# design.net
KiCad netlist of a schematic drawn in Altium Designer
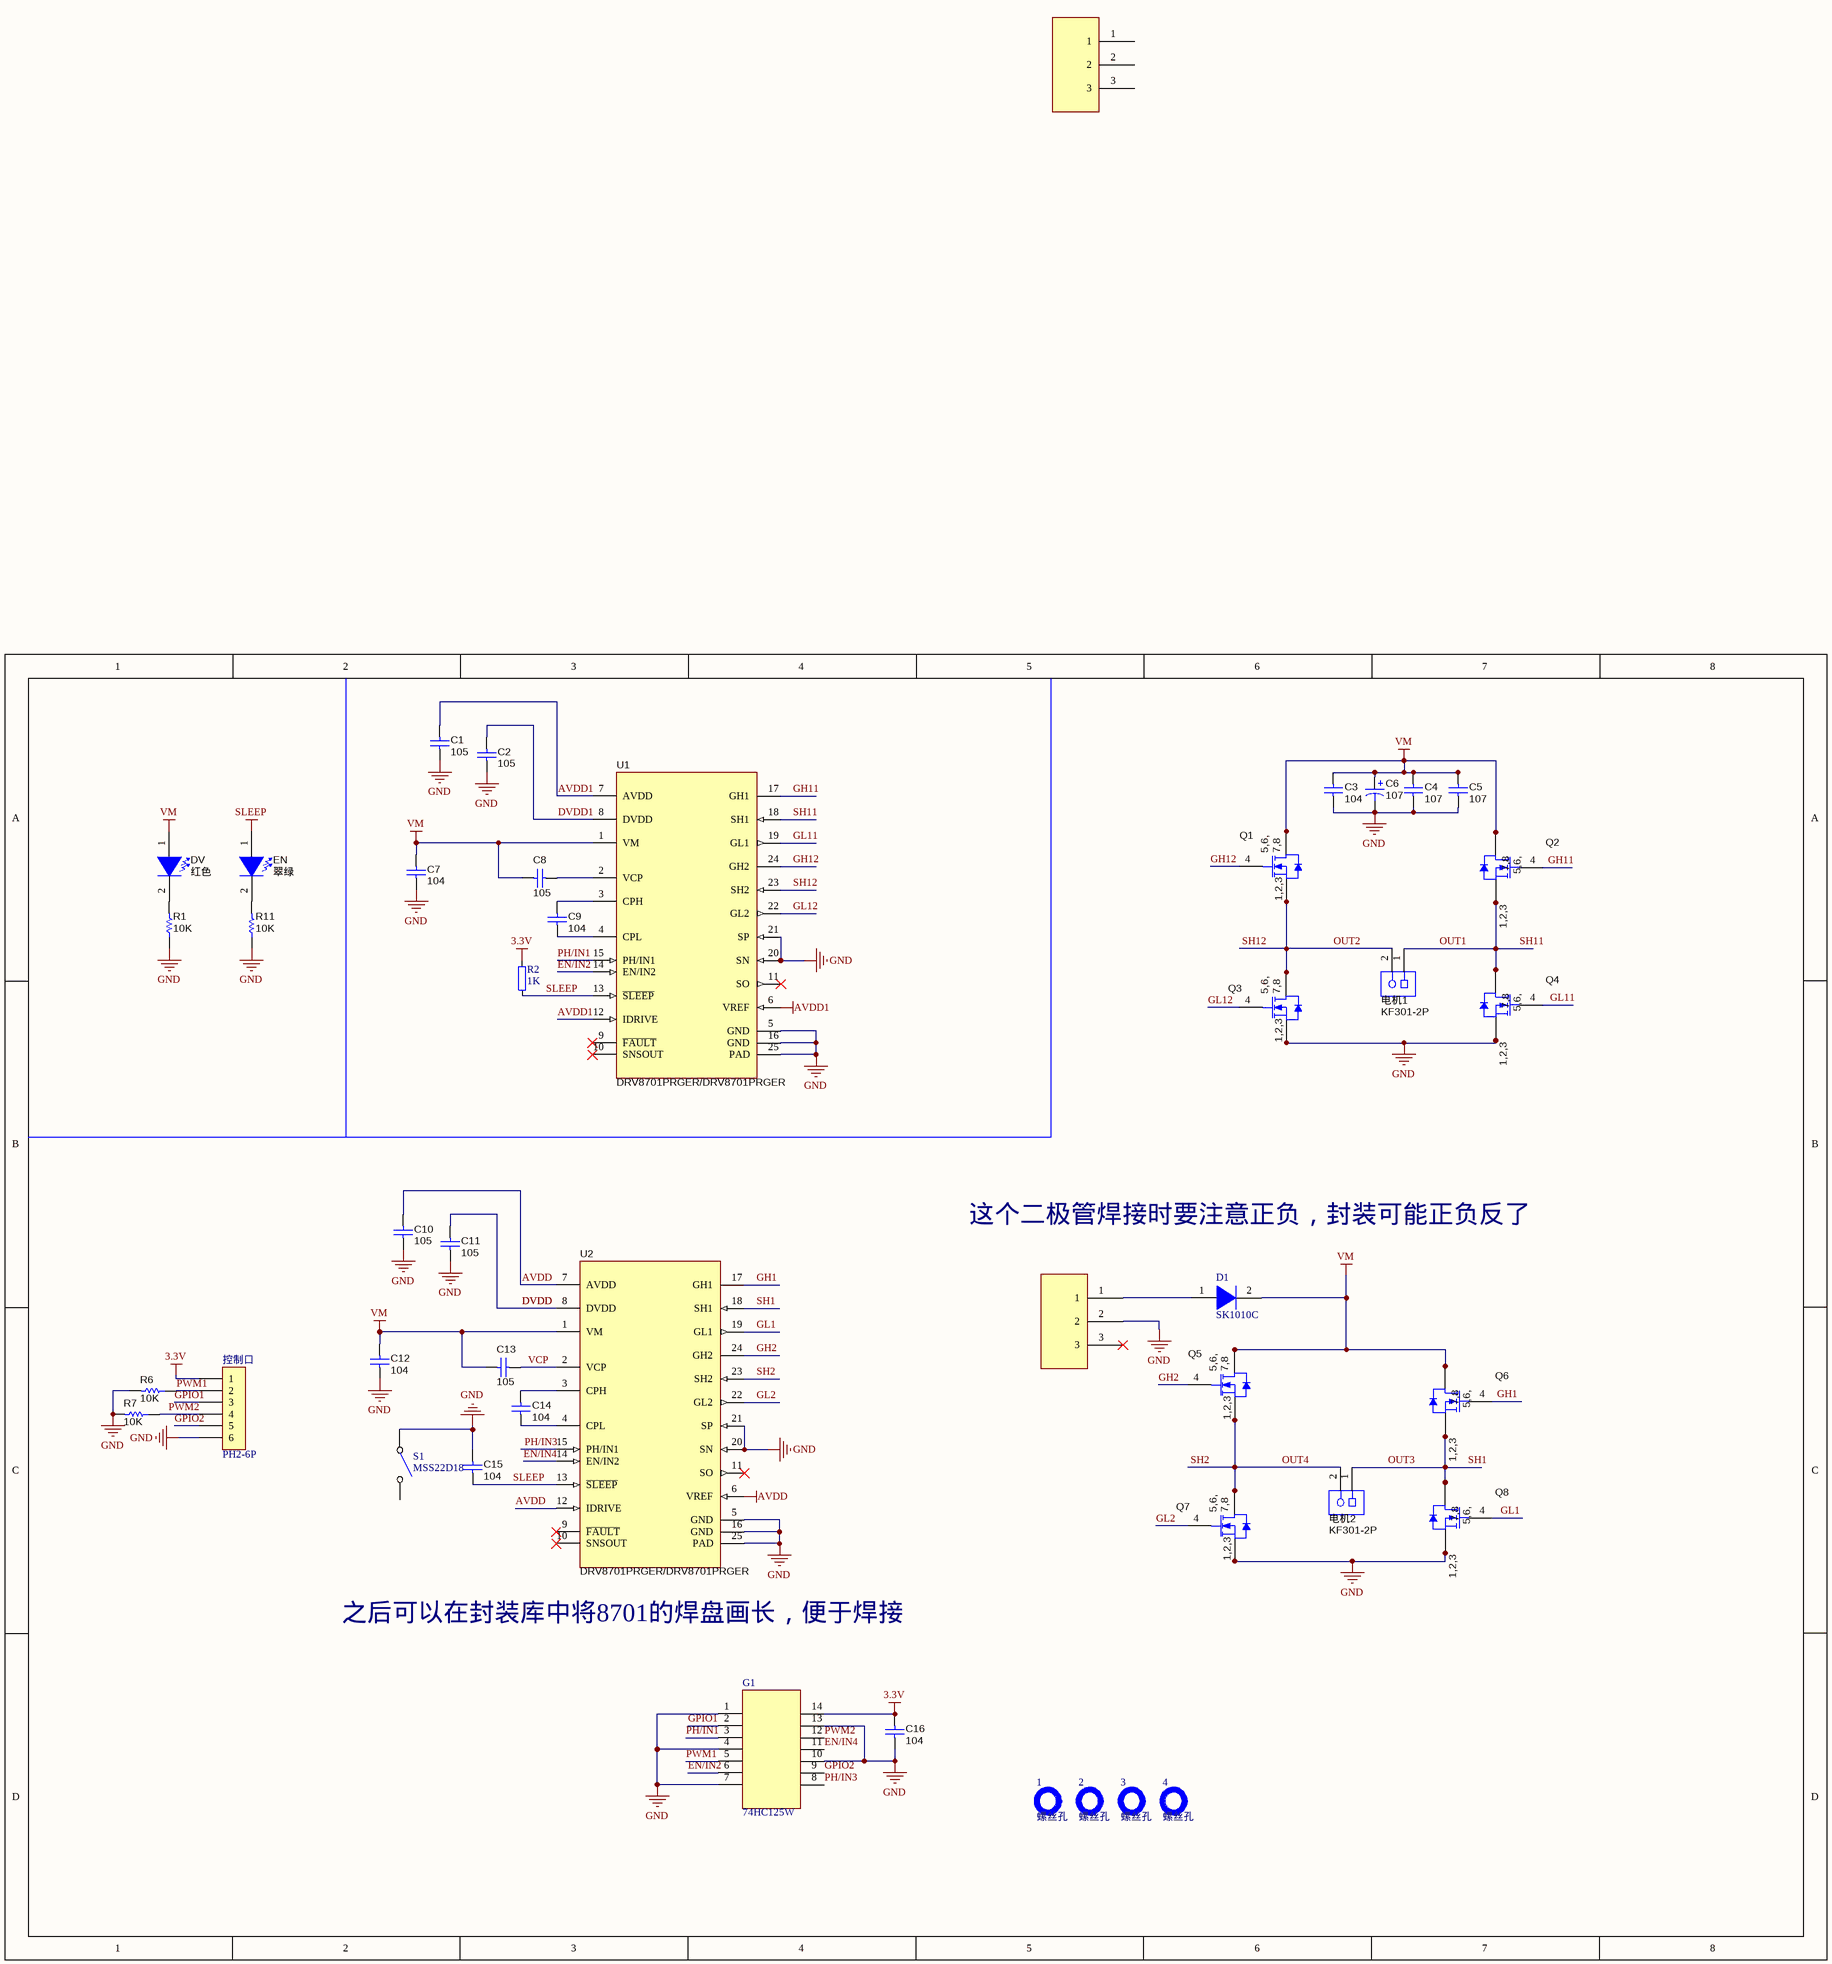
[diagram p0: 精简版双路驱动.SchDoc]

(export (version "E")
  (design (tool "Eeschema 10.0.6"))
  (components
    (comp (ref "*") (value "DC接口") (libsource (lib "LQ8701") (part "DC接口")))
    (comp (ref "1") (value "螺丝孔") (footprint "LQ_SCROW3&5MM") (libsource (lib "LQ8701") (part "螺丝孔")))
    (comp (ref "2") (value "螺丝孔") (footprint "LQ_SCROW3&5MM") (libsource (lib "LQ8701") (part "螺丝孔")))
    (comp (ref "3") (value "螺丝孔") (footprint "LQ_SCROW3&5MM") (libsource (lib "LQ8701") (part "螺丝孔")))
    (comp (ref "4") (value "螺丝孔") (footprint "LQ_SCROW3&5MM") (libsource (lib "LQ8701") (part "螺丝孔")))
    (comp (ref "C1")
      (value "105")
      (footprint "LQ_C0603")
      (fields
        (field (name "PARTNUMBER") "GRM188R70J105KA01D")
        (field (name "MANUFACTURER") "MuRata")
        (field (name "PUBLISHER") "Texas Instruments")
      )
      (libsource (lib "LQ8701") (part "GRM188R70J105KA01D"))
    )
    (comp (ref "C2")
      (value "105")
      (footprint "LQ_C0603")
      (fields
        (field (name "PARTNUMBER") "GRM188R70J105KA01D")
        (field (name "MANUFACTURER") "MuRata")
        (field (name "PUBLISHER") "Texas Instruments")
      )
      (libsource (lib "LQ8701") (part "GRM188R70J105KA01D"))
    )
    (comp (ref "C3")
      (value "104")
      (footprint "LQ_C0603")
      (fields
        (field (name "PARTNUMBER") "GRM21BR71H105KA12L")
        (field (name "MANUFACTURER") "MuRata")
        (field (name "PUBLISHER") "Texas Instruments")
      )
      (libsource (lib "LQ8701") (part "GRM21BR71H105KA12L"))
    )
    (comp (ref "C4")
      (value "107")
      (footprint "LQ_C1210")
      (fields
        (field (name "PARTNUMBER") "GRM21BR71H105KA12L")
        (field (name "MANUFACTURER") "MuRata")
        (field (name "PUBLISHER") "Texas Instruments")
      )
      (libsource (lib "LQ8701") (part "GRM21BR71H105KA12L"))
    )
    (comp (ref "C5")
      (value "107")
      (footprint "LQ_C1210")
      (fields
        (field (name "PARTNUMBER") "GRM21BR71H105KA12L")
        (field (name "MANUFACTURER") "MuRata")
        (field (name "PUBLISHER") "Texas Instruments")
      )
      (libsource (lib "LQ8701") (part "GRM21BR71H105KA12L"))
    )
    (comp (ref "C6")
      (value "107")
      (footprint "LQ_C1210")
      (fields
        (field (name "PARTNUMBER") "ECA-1HM471")
        (field (name "MANUFACTURER") "Panasonic")
        (field (name "PUBLISHER") "Texas Instruments")
      )
      (libsource (lib "LQ8701") (part "ECA-1HM471"))
    )
    (comp (ref "C7")
      (value "104")
      (footprint "LQ_C0603")
      (fields
        (field (name "PARTNUMBER") "GRM21BR71H105KA12L")
        (field (name "MANUFACTURER") "MuRata")
        (field (name "PUBLISHER") "Texas Instruments")
      )
      (libsource (lib "LQ8701") (part "GRM21BR71H105KA12L"))
    )
    (comp (ref "C8")
      (value "105")
      (footprint "LQ_C0603")
      (fields
        (field (name "PARTNUMBER") "GRM188R70J105KA01D")
        (field (name "MANUFACTURER") "MuRata")
        (field (name "PUBLISHER") "Texas Instruments")
      )
      (libsource (lib "LQ8701") (part "GRM188R70J105KA01D"))
    )
    (comp (ref "C9")
      (value "104")
      (footprint "LQ_C0603")
      (fields
        (field (name "PARTNUMBER") "GRM21BR71H105KA12L")
        (field (name "MANUFACTURER") "MuRata")
        (field (name "PUBLISHER") "Texas Instruments")
      )
      (libsource (lib "LQ8701") (part "GRM21BR71H105KA12L"))
    )
    (comp (ref "C10")
      (value "105")
      (footprint "LQ_C0603")
      (fields
        (field (name "PARTNUMBER") "GRM188R70J105KA01D")
        (field (name "MANUFACTURER") "MuRata")
        (field (name "PUBLISHER") "Texas Instruments")
      )
      (libsource (lib "LQ8701") (part "GRM188R70J105KA01D"))
    )
    (comp (ref "C11")
      (value "105")
      (footprint "LQ_C0603")
      (fields
        (field (name "PARTNUMBER") "GRM188R70J105KA01D")
        (field (name "MANUFACTURER") "MuRata")
        (field (name "PUBLISHER") "Texas Instruments")
      )
      (libsource (lib "LQ8701") (part "GRM188R70J105KA01D"))
    )
    (comp (ref "C12")
      (value "104")
      (footprint "LQ_C0603")
      (fields
        (field (name "PARTNUMBER") "GRM21BR71H105KA12L")
        (field (name "MANUFACTURER") "MuRata")
        (field (name "PUBLISHER") "Texas Instruments")
      )
      (libsource (lib "LQ8701") (part "GRM21BR71H105KA12L"))
    )
    (comp (ref "C13")
      (value "105")
      (footprint "LQ_C0603")
      (fields
        (field (name "PARTNUMBER") "GRM188R70J105KA01D")
        (field (name "MANUFACTURER") "MuRata")
        (field (name "PUBLISHER") "Texas Instruments")
      )
      (libsource (lib "LQ8701") (part "GRM188R70J105KA01D"))
    )
    (comp (ref "C14")
      (value "104")
      (footprint "LQ_C0603")
      (fields
        (field (name "PARTNUMBER") "GRM21BR71H105KA12L")
        (field (name "MANUFACTURER") "MuRata")
        (field (name "PUBLISHER") "Texas Instruments")
      )
      (libsource (lib "LQ8701") (part "GRM21BR71H105KA12L"))
    )
    (comp (ref "C15")
      (value "104")
      (footprint "LQ_C0603")
      (fields
        (field (name "PARTNUMBER") "GRM21BR71H105KA12L")
        (field (name "MANUFACTURER") "MuRata")
        (field (name "PUBLISHER") "Texas Instruments")
      )
      (libsource (lib "LQ8701") (part "GRM21BR71H105KA12L"))
    )
    (comp (ref "C16")
      (value "104")
      (footprint "LQ_C0603")
      (fields
        (field (name "PARTNUMBER") "GRM21BR71H105KA12L")
        (field (name "MANUFACTURER") "MuRata")
        (field (name "PUBLISHER") "Texas Instruments")
      )
      (libsource (lib "LQ8701") (part "GRM21BR71H105KA12L"))
    )
    (comp (ref "D1")
      (value "SK1010C")
      (footprint "LQ_DSMC-DO-214AB")
      (libsource (lib "LQ8701") (part "SK1010C"))
    )
    (comp (ref "DV")
      (value "红色")
      (footprint "LQ_LED0603R")
      (fields
        (field (name "MANUFACTURER") "Lite-On")
        (field (name "PARTNUMBER") "LTST-C171GKT")
        (field (name "PUBLISHER") "Texas Instruments")
      )
      (libsource (lib "LQ8701") (part "LTST-C171GKT"))
    )
    (comp (ref "EN")
      (value "翠绿")
      (footprint "LQ_LED0603R")
      (fields
        (field (name "MANUFACTURER") "Lite-On")
        (field (name "PARTNUMBER") "LTST-C171GKT")
        (field (name "PUBLISHER") "Texas Instruments")
      )
      (libsource (lib "LQ8701") (part "LTST-C171GKT"))
    )
    (comp (ref "G1")
      (value "74HC125W")
      (footprint "TSOP65P640X110-14N")
      (libsource (lib "LQ8701") (part "74HC125W"))
    )
    (comp (ref "J1") (value "DC接口") (footprint "DC-005") (libsource (lib "LQ8701") (part "DC接口")))
    (comp (ref "Q1")
      (value "TPH1R403NL/CSD18532Q5B")
      (footprint "LQ_SON5X6")
      (fields
        (field (name "PARTNUMBER") "CSD18532Q5B")
        (field (name "MANUFACTURER") "Texas Instruments")
        (field (name "PUBLISHER") "Texas Instruments")
      )
      (libsource (lib "LQ8701") (part "CSD18532Q5B"))
    )
    (comp (ref "Q2")
      (value "TPH1R403NL/CSD18532Q5B")
      (footprint "LQ_SON5X6")
      (fields
        (field (name "PARTNUMBER") "CSD18532Q5B")
        (field (name "MANUFACTURER") "Texas Instruments")
        (field (name "PUBLISHER") "Texas Instruments")
      )
      (libsource (lib "LQ8701") (part "CSD18532Q5B"))
    )
    (comp (ref "Q3")
      (value "TPH1R403NL/CSD18532Q5B")
      (footprint "LQ_SON5X6")
      (fields
        (field (name "PARTNUMBER") "CSD18532Q5B")
        (field (name "MANUFACTURER") "Texas Instruments")
        (field (name "PUBLISHER") "Texas Instruments")
      )
      (libsource (lib "LQ8701") (part "CSD18532Q5B"))
    )
    (comp (ref "Q4")
      (value "TPH1R403NL/CSD18532Q5B")
      (footprint "LQ_SON5X6")
      (fields
        (field (name "PARTNUMBER") "CSD18532Q5B")
        (field (name "MANUFACTURER") "Texas Instruments")
        (field (name "PUBLISHER") "Texas Instruments")
      )
      (libsource (lib "LQ8701") (part "CSD18532Q5B"))
    )
    (comp (ref "Q5")
      (value "TPH1R403NL/CSD18532Q5B")
      (footprint "LQ_SON5X6")
      (fields
        (field (name "PARTNUMBER") "CSD18532Q5B")
        (field (name "MANUFACTURER") "Texas Instruments")
        (field (name "PUBLISHER") "Texas Instruments")
      )
      (libsource (lib "LQ8701") (part "CSD18532Q5B"))
    )
    (comp (ref "Q6")
      (value "TPH1R403NL/CSD18532Q5B")
      (footprint "LQ_SON5X6")
      (fields
        (field (name "PARTNUMBER") "CSD18532Q5B")
        (field (name "MANUFACTURER") "Texas Instruments")
        (field (name "PUBLISHER") "Texas Instruments")
      )
      (libsource (lib "LQ8701") (part "CSD18532Q5B"))
    )
    (comp (ref "Q7")
      (value "TPH1R403NL/CSD18532Q5B")
      (footprint "LQ_SON5X6")
      (fields
        (field (name "PARTNUMBER") "CSD18532Q5B")
        (field (name "MANUFACTURER") "Texas Instruments")
        (field (name "PUBLISHER") "Texas Instruments")
      )
      (libsource (lib "LQ8701") (part "CSD18532Q5B"))
    )
    (comp (ref "Q8")
      (value "TPH1R403NL/CSD18532Q5B")
      (footprint "LQ_SON5X6")
      (fields
        (field (name "PARTNUMBER") "CSD18532Q5B")
        (field (name "MANUFACTURER") "Texas Instruments")
        (field (name "PUBLISHER") "Texas Instruments")
      )
      (libsource (lib "LQ8701") (part "CSD18532Q5B"))
    )
    (comp (ref "R1")
      (value "10K")
      (footprint "LQ_R0603")
      (fields
        (field (name "PARTNUMBER") "CRCW06034K99FKEA")
        (field (name "MANUFACTURER") "Vishay-Dale")
        (field (name "PUBLISHER") "Texas Instruments")
      )
      (libsource (lib "LQ8701") (part "CRCW06034K99FKEA"))
    )
    (comp (ref "R2") (value "1K") (footprint "LQ_R0603") (libsource (lib "LQ8701") (part "RES")))
    (comp (ref "R6")
      (value "10K")
      (footprint "LQ_R0603")
      (fields
        (field (name "PARTNUMBER") "CRCW06034K99FKEA")
        (field (name "MANUFACTURER") "Vishay-Dale")
        (field (name "PUBLISHER") "Texas Instruments")
      )
      (libsource (lib "LQ8701") (part "CRCW06034K99FKEA"))
    )
    (comp (ref "R7")
      (value "10K")
      (footprint "LQ_R0603")
      (fields
        (field (name "PARTNUMBER") "CRCW06034K99FKEA")
        (field (name "MANUFACTURER") "Vishay-Dale")
        (field (name "PUBLISHER") "Texas Instruments")
      )
      (libsource (lib "LQ8701") (part "CRCW06034K99FKEA"))
    )
    (comp (ref "R11")
      (value "10K")
      (footprint "LQ_R0603")
      (fields
        (field (name "PARTNUMBER") "CRCW06034K99FKEA")
        (field (name "MANUFACTURER") "Vishay-Dale")
        (field (name "PUBLISHER") "Texas Instruments")
      )
      (libsource (lib "LQ8701") (part "CRCW06034K99FKEA"))
    )
    (comp (ref "S1")
      (value "MSS22D18")
      (footprint "LQ_SW_MSS22D18")
      (libsource (lib "LQ8701") (part "SW SPST"))
    )
    (comp (ref "U1")
      (value "DRV8701PRGER/DRV8701PRGER")
      (footprint "RGE0024F")
      (fields
        (field (name "PARTNUMBER") "DRV8701ERGER")
        (field (name "ALTERNATE PARTNUMBER") "DRV8701ERGET")
        (field (name "MANUFACTURER") "Texas Instruments")
        (field (name "SYMBOLCREATOR") "Altium")
        (field (name "PUBLISHER") "Texas Instruments")
      )
      (libsource (lib "LQ8701") (part "DRV8701ERGER"))
    )
    (comp (ref "U2")
      (value "DRV8701PRGER/DRV8701PRGER")
      (footprint "RGE0024F")
      (fields
        (field (name "PARTNUMBER") "DRV8701ERGER")
        (field (name "ALTERNATE PARTNUMBER") "DRV8701ERGET")
        (field (name "MANUFACTURER") "Texas Instruments")
        (field (name "SYMBOLCREATOR") "Altium")
        (field (name "PUBLISHER") "Texas Instruments")
      )
      (libsource (lib "LQ8701") (part "DRV8701ERGER"))
    )
    (comp (ref "控制口") (value "PH2-6P") (footprint "LQ_PH2.0-WI-6P") (libsource (lib "LQ8701") (part "控制口")))
    (comp (ref "电机1")
      (value "KF301-2P")
      (footprint "TX60-LI-S")
      (fields
        (field (name "PARTNUMBER") "691 101 710 002")
        (field (name "MANUFACTURER") "Wurth Elektronik eiSos")
        (field (name "SYMBOLCREATOR") "a0412235")
        (field (name "PUBLISHER") "Texas Instruments")
      )
      (libsource (lib "LQ8701") (part "691 101 710 002"))
    )
    (comp (ref "电机2")
      (value "KF301-2P")
      (footprint "TX60-LI-S")
      (fields
        (field (name "PARTNUMBER") "691 101 710 002")
        (field (name "MANUFACTURER") "Wurth Elektronik eiSos")
        (field (name "SYMBOLCREATOR") "a0412235")
        (field (name "PUBLISHER") "Texas Instruments")
      )
      (libsource (lib "LQ8701") (part "691 101 710 002"))
    )
  )
  (nets
    (net (code "1") (name "/DVDD") (class "Default")
      (node (ref "C11") (pin "1") (pinfunction "1_1") (pintype "passive"))
      (node (ref "U2") (pin "8") (pinfunction "DVDD_8") (pintype "power_in"))
    )
    (net (code "2") (name "/DVDD1") (class "Default")
      (node (ref "C2") (pin "1") (pinfunction "1_1") (pintype "passive"))
      (node (ref "U1") (pin "8") (pinfunction "DVDD_8") (pintype "power_in"))
    )
    (net (code "3") (name "/EN{slash}IN2") (class "Default")
      (node (ref "G1") (pin "6") (pinfunction "6_6") (pintype "passive"))
      (node (ref "U1") (pin "14") (pinfunction "EN/IN2_14") (pintype "input"))
    )
    (net (code "4") (name "/EN{slash}IN4") (class "Default")
      (node (ref "G1") (pin "11") (pinfunction "11_11") (pintype "passive"))
      (node (ref "U2") (pin "14") (pinfunction "EN/IN2_14") (pintype "input"))
    )
    (net (code "5") (name "/GH1") (class "Default")
      (node (ref "Q6") (pin "4") (pinfunction "G_4") (pintype "passive"))
      (node (ref "U2") (pin "17") (pinfunction "GH1_17") (pintype "power_in"))
    )
    (net (code "6") (name "/GH2") (class "Default")
      (node (ref "Q5") (pin "4") (pinfunction "G_4") (pintype "passive"))
      (node (ref "U2") (pin "24") (pinfunction "GH2_24") (pintype "power_in"))
    )
    (net (code "7") (name "/GH11") (class "Default")
      (node (ref "Q2") (pin "4") (pinfunction "G_4") (pintype "passive"))
      (node (ref "U1") (pin "17") (pinfunction "GH1_17") (pintype "power_in"))
    )
    (net (code "8") (name "/GH12") (class "Default")
      (node (ref "Q1") (pin "4") (pinfunction "G_4") (pintype "passive"))
      (node (ref "U1") (pin "24") (pinfunction "GH2_24") (pintype "power_in"))
    )
    (net (code "9") (name "/GL1") (class "Default")
      (node (ref "Q8") (pin "4") (pinfunction "G_4") (pintype "passive"))
      (node (ref "U2") (pin "19") (pinfunction "GL1_19") (pintype "output"))
    )
    (net (code "10") (name "/GL2") (class "Default")
      (node (ref "Q7") (pin "4") (pinfunction "G_4") (pintype "passive"))
      (node (ref "U2") (pin "22") (pinfunction "GL2_22") (pintype "output"))
    )
    (net (code "11") (name "/GL11") (class "Default")
      (node (ref "Q4") (pin "4") (pinfunction "G_4") (pintype "passive"))
      (node (ref "U1") (pin "19") (pinfunction "GL1_19") (pintype "output"))
    )
    (net (code "12") (name "/GL12") (class "Default")
      (node (ref "Q3") (pin "4") (pinfunction "G_4") (pintype "passive"))
      (node (ref "U1") (pin "22") (pinfunction "GL2_22") (pintype "output"))
    )
    (net (code "13") (name "/GPIO1") (class "Default")
      (node (ref "G1") (pin "2") (pinfunction "2_2") (pintype "passive"))
      (node (ref "控制口") (pin "3") (pinfunction "3_3") (pintype "passive"))
    )
    (net (code "14") (name "/GPIO2") (class "Default")
      (node (ref "G1") (pin "9") (pinfunction "9_9") (pintype "passive"))
      (node (ref "控制口") (pin "5") (pinfunction "5_5") (pintype "passive"))
    )
    (net (code "15") (name "/OUT1") (class "Default")
      (node (ref "Q2") (pin "1") (pinfunction "S_1") (pintype "passive"))
      (node (ref "Q2") (pin "2") (pinfunction "S_2") (pintype "passive"))
      (node (ref "Q2") (pin "3") (pinfunction "S_3") (pintype "passive"))
      (node (ref "Q4") (pin "5") (pinfunction "D_5") (pintype "passive"))
      (node (ref "Q4") (pin "6") (pinfunction "D_6") (pintype "passive"))
      (node (ref "Q4") (pin "7") (pinfunction "D_7") (pintype "passive"))
      (node (ref "Q4") (pin "8") (pinfunction "D_8") (pintype "passive"))
      (node (ref "U1") (pin "18") (pinfunction "SH1_18") (pintype "input"))
      (node (ref "电机1") (pin "1") (pinfunction "1_1") (pintype "passive"))
    )
    (net (code "16") (name "/OUT2") (class "Default")
      (node (ref "Q1") (pin "1") (pinfunction "S_1") (pintype "passive"))
      (node (ref "Q1") (pin "2") (pinfunction "S_2") (pintype "passive"))
      (node (ref "Q1") (pin "3") (pinfunction "S_3") (pintype "passive"))
      (node (ref "Q3") (pin "5") (pinfunction "D_5") (pintype "passive"))
      (node (ref "Q3") (pin "6") (pinfunction "D_6") (pintype "passive"))
      (node (ref "Q3") (pin "7") (pinfunction "D_7") (pintype "passive"))
      (node (ref "Q3") (pin "8") (pinfunction "D_8") (pintype "passive"))
      (node (ref "U1") (pin "23") (pinfunction "SH2_23") (pintype "input"))
      (node (ref "电机1") (pin "2") (pinfunction "2_2") (pintype "passive"))
    )
    (net (code "17") (name "/OUT3") (class "Default")
      (node (ref "Q6") (pin "1") (pinfunction "S_1") (pintype "passive"))
      (node (ref "Q6") (pin "2") (pinfunction "S_2") (pintype "passive"))
      (node (ref "Q6") (pin "3") (pinfunction "S_3") (pintype "passive"))
      (node (ref "Q8") (pin "5") (pinfunction "D_5") (pintype "passive"))
      (node (ref "Q8") (pin "6") (pinfunction "D_6") (pintype "passive"))
      (node (ref "Q8") (pin "7") (pinfunction "D_7") (pintype "passive"))
      (node (ref "Q8") (pin "8") (pinfunction "D_8") (pintype "passive"))
      (node (ref "U2") (pin "18") (pinfunction "SH1_18") (pintype "input"))
      (node (ref "电机2") (pin "1") (pinfunction "1_1") (pintype "passive"))
    )
    (net (code "18") (name "/OUT4") (class "Default")
      (node (ref "Q5") (pin "1") (pinfunction "S_1") (pintype "passive"))
      (node (ref "Q5") (pin "2") (pinfunction "S_2") (pintype "passive"))
      (node (ref "Q5") (pin "3") (pinfunction "S_3") (pintype "passive"))
      (node (ref "Q7") (pin "5") (pinfunction "D_5") (pintype "passive"))
      (node (ref "Q7") (pin "6") (pinfunction "D_6") (pintype "passive"))
      (node (ref "Q7") (pin "7") (pinfunction "D_7") (pintype "passive"))
      (node (ref "Q7") (pin "8") (pinfunction "D_8") (pintype "passive"))
      (node (ref "U2") (pin "23") (pinfunction "SH2_23") (pintype "input"))
      (node (ref "电机2") (pin "2") (pinfunction "2_2") (pintype "passive"))
    )
    (net (code "19") (name "/PH{slash}IN1") (class "Default")
      (node (ref "G1") (pin "3") (pinfunction "3_3") (pintype "passive"))
      (node (ref "U1") (pin "15") (pinfunction "PH/IN1_15") (pintype "input"))
    )
    (net (code "20") (name "/PH{slash}IN3") (class "Default")
      (node (ref "G1") (pin "8") (pinfunction "8_8") (pintype "passive"))
      (node (ref "U2") (pin "15") (pinfunction "PH/IN1_15") (pintype "input"))
    )
    (net (code "21") (name "/PWM1") (class "Default")
      (node (ref "G1") (pin "5") (pinfunction "5_5") (pintype "passive"))
      (node (ref "R6") (pin "1") (pinfunction "1_1") (pintype "passive"))
      (node (ref "控制口") (pin "2") (pinfunction "2_2") (pintype "passive"))
    )
    (net (code "22") (name "/PWM2") (class "Default")
      (node (ref "G1") (pin "12") (pinfunction "12_12") (pintype "passive"))
      (node (ref "R7") (pin "1") (pinfunction "1_1") (pintype "passive"))
      (node (ref "控制口") (pin "4") (pinfunction "4_4") (pintype "passive"))
    )
    (net (code "23") (name "/VCP") (class "Default")
      (node (ref "C13") (pin "1") (pinfunction "1_1") (pintype "passive"))
      (node (ref "U2") (pin "2") (pinfunction "VCP_2") (pintype "power_in"))
    )
    (net (code "24") (name "3.3V") (class "Default")
      (node (ref "C16") (pin "1") (pinfunction "1_1") (pintype "passive"))
      (node (ref "G1") (pin "14") (pinfunction "14_14") (pintype "passive"))
      (node (ref "R2") (pin "2") (pinfunction "2_2") (pintype "passive"))
      (node (ref "控制口") (pin "1") (pinfunction "1_1") (pintype "passive"))
    )
    (net (code "25") (name "AVDD") (class "Default")
      (node (ref "C10") (pin "1") (pinfunction "1_1") (pintype "passive"))
      (node (ref "U2") (pin "12") (pinfunction "IDRIVE_12") (pintype "input"))
      (node (ref "U2") (pin "6") (pinfunction "VREF_6") (pintype "input"))
      (node (ref "U2") (pin "7") (pinfunction "AVDD_7") (pintype "power_in"))
    )
    (net (code "26") (name "AVDD1") (class "Default")
      (node (ref "C1") (pin "1") (pinfunction "1_1") (pintype "passive"))
      (node (ref "U1") (pin "12") (pinfunction "IDRIVE_12") (pintype "input"))
      (node (ref "U1") (pin "6") (pinfunction "VREF_6") (pintype "input"))
      (node (ref "U1") (pin "7") (pinfunction "AVDD_7") (pintype "power_in"))
    )
    (net (code "27") (name "GND") (class "Default")
      (node (ref "C1") (pin "2") (pinfunction "2_2") (pintype "passive"))
      (node (ref "C10") (pin "2") (pinfunction "2_2") (pintype "passive"))
      (node (ref "C11") (pin "2") (pinfunction "2_2") (pintype "passive"))
      (node (ref "C12") (pin "2") (pinfunction "2_2") (pintype "passive"))
      (node (ref "C15") (pin "1") (pinfunction "1_1") (pintype "passive"))
      (node (ref "C16") (pin "2") (pinfunction "2_2") (pintype "passive"))
      (node (ref "C2") (pin "2") (pinfunction "2_2") (pintype "passive"))
      (node (ref "C3") (pin "2") (pinfunction "2_2") (pintype "passive"))
      (node (ref "C4") (pin "2") (pinfunction "2_2") (pintype "passive"))
      (node (ref "C5") (pin "2") (pinfunction "2_2") (pintype "passive"))
      (node (ref "C6") (pin "2") (pinfunction "-_2") (pintype "passive"))
      (node (ref "C7") (pin "2") (pinfunction "2_2") (pintype "passive"))
      (node (ref "G1") (pin "1") (pinfunction "1_1") (pintype "passive"))
      (node (ref "G1") (pin "10") (pinfunction "10_10") (pintype "passive"))
      (node (ref "G1") (pin "13") (pinfunction "13_13") (pintype "passive"))
      (node (ref "G1") (pin "4") (pinfunction "4_4") (pintype "passive"))
      (node (ref "G1") (pin "7") (pinfunction "7_7") (pintype "passive"))
      (node (ref "J1") (pin "2") (pinfunction "2_2") (pintype "passive"))
      (node (ref "Q3") (pin "1") (pinfunction "S_1") (pintype "passive"))
      (node (ref "Q3") (pin "2") (pinfunction "S_2") (pintype "passive"))
      (node (ref "Q3") (pin "3") (pinfunction "S_3") (pintype "passive"))
      (node (ref "Q4") (pin "1") (pinfunction "S_1") (pintype "passive"))
      (node (ref "Q4") (pin "2") (pinfunction "S_2") (pintype "passive"))
      (node (ref "Q4") (pin "3") (pinfunction "S_3") (pintype "passive"))
      (node (ref "Q7") (pin "1") (pinfunction "S_1") (pintype "passive"))
      (node (ref "Q7") (pin "2") (pinfunction "S_2") (pintype "passive"))
      (node (ref "Q7") (pin "3") (pinfunction "S_3") (pintype "passive"))
      (node (ref "Q8") (pin "1") (pinfunction "S_1") (pintype "passive"))
      (node (ref "Q8") (pin "2") (pinfunction "S_2") (pintype "passive"))
      (node (ref "Q8") (pin "3") (pinfunction "S_3") (pintype "passive"))
      (node (ref "R1") (pin "1") (pinfunction "1_1") (pintype "passive"))
      (node (ref "R11") (pin "1") (pinfunction "1_1") (pintype "passive"))
      (node (ref "R6") (pin "2") (pinfunction "2_2") (pintype "passive"))
      (node (ref "R7") (pin "2") (pinfunction "2_2") (pintype "passive"))
      (node (ref "S1") (pin "1") (pinfunction "COMMON_1") (pintype "passive"))
      (node (ref "U1") (pin "16") (pinfunction "GND_16") (pintype "power_in"))
      (node (ref "U1") (pin "20") (pinfunction "SN_20") (pintype "input"))
      (node (ref "U1") (pin "21") (pinfunction "SP_21") (pintype "input"))
      (node (ref "U1") (pin "25") (pinfunction "PAD_25") (pintype "power_in"))
      (node (ref "U1") (pin "5") (pinfunction "GND_5") (pintype "power_in"))
      (node (ref "U2") (pin "16") (pinfunction "GND_16") (pintype "power_in"))
      (node (ref "U2") (pin "20") (pinfunction "SN_20") (pintype "input"))
      (node (ref "U2") (pin "21") (pinfunction "SP_21") (pintype "input"))
      (node (ref "U2") (pin "25") (pinfunction "PAD_25") (pintype "power_in"))
      (node (ref "U2") (pin "5") (pinfunction "GND_5") (pintype "power_in"))
      (node (ref "控制口") (pin "6") (pinfunction "6_6") (pintype "passive"))
    )
    (net (code "28") (name "Net-(D1-A)") (class "Default")
      (node (ref "D1") (pin "1") (pinfunction "A_1") (pintype "passive"))
      (node (ref "J1") (pin "1") (pinfunction "1_1") (pintype "passive"))
    )
    (net (code "29") (name "Net-(DV-K)") (class "Default")
      (node (ref "DV") (pin "2") (pinfunction "K_2") (pintype "passive"))
      (node (ref "R1") (pin "2") (pinfunction "2_2") (pintype "passive"))
    )
    (net (code "30") (name "Net-(EN-K)") (class "Default")
      (node (ref "EN") (pin "2") (pinfunction "K_2") (pintype "passive"))
      (node (ref "R11") (pin "2") (pinfunction "2_2") (pintype "passive"))
    )
    (net (code "31") (name "Net-(U1-CPH)") (class "Default")
      (node (ref "C9") (pin "1") (pinfunction "1_1") (pintype "passive"))
      (node (ref "U1") (pin "3") (pinfunction "CPH_3") (pintype "passive"))
    )
    (net (code "32") (name "Net-(U1-CPL)") (class "Default")
      (node (ref "C9") (pin "2") (pinfunction "2_2") (pintype "passive"))
      (node (ref "U1") (pin "4") (pinfunction "CPL_4") (pintype "passive"))
    )
    (net (code "33") (name "Net-(U1-VCP)") (class "Default")
      (node (ref "C8") (pin "1") (pinfunction "1_1") (pintype "passive"))
      (node (ref "U1") (pin "2") (pinfunction "VCP_2") (pintype "power_in"))
    )
    (net (code "34") (name "Net-(U2-CPH)") (class "Default")
      (node (ref "C14") (pin "1") (pinfunction "1_1") (pintype "passive"))
      (node (ref "U2") (pin "3") (pinfunction "CPH_3") (pintype "passive"))
    )
    (net (code "35") (name "Net-(U2-CPL)") (class "Default")
      (node (ref "C14") (pin "2") (pinfunction "2_2") (pintype "passive"))
      (node (ref "U2") (pin "4") (pinfunction "CPL_4") (pintype "passive"))
    )
    (net (code "36") (name "SLEEP") (class "Default")
      (node (ref "C15") (pin "2") (pinfunction "2_2") (pintype "passive"))
      (node (ref "EN") (pin "1") (pinfunction "A_1") (pintype "passive"))
      (node (ref "R2") (pin "1") (pinfunction "1_1") (pintype "passive"))
      (node (ref "U1") (pin "13") (pinfunction "SLEEP_13") (pintype "input"))
      (node (ref "U2") (pin "13") (pinfunction "SLEEP_13") (pintype "input"))
    )
    (net (code "37") (name "VM") (class "Default")
      (node (ref "C12") (pin "1") (pinfunction "1_1") (pintype "passive"))
      (node (ref "C13") (pin "2") (pinfunction "2_2") (pintype "passive"))
      (node (ref "C3") (pin "1") (pinfunction "1_1") (pintype "passive"))
      (node (ref "C4") (pin "1") (pinfunction "1_1") (pintype "passive"))
      (node (ref "C5") (pin "1") (pinfunction "1_1") (pintype "passive"))
      (node (ref "C6") (pin "1") (pinfunction "+_1") (pintype "passive"))
      (node (ref "C7") (pin "1") (pinfunction "1_1") (pintype "passive"))
      (node (ref "C8") (pin "2") (pinfunction "2_2") (pintype "passive"))
      (node (ref "D1") (pin "2") (pinfunction "K_2") (pintype "passive"))
      (node (ref "DV") (pin "1") (pinfunction "A_1") (pintype "passive"))
      (node (ref "Q1") (pin "5") (pinfunction "D_5") (pintype "passive"))
      (node (ref "Q1") (pin "6") (pinfunction "D_6") (pintype "passive"))
      (node (ref "Q1") (pin "7") (pinfunction "D_7") (pintype "passive"))
      (node (ref "Q1") (pin "8") (pinfunction "D_8") (pintype "passive"))
      (node (ref "Q2") (pin "5") (pinfunction "D_5") (pintype "passive"))
      (node (ref "Q2") (pin "6") (pinfunction "D_6") (pintype "passive"))
      (node (ref "Q2") (pin "7") (pinfunction "D_7") (pintype "passive"))
      (node (ref "Q2") (pin "8") (pinfunction "D_8") (pintype "passive"))
      (node (ref "Q5") (pin "5") (pinfunction "D_5") (pintype "passive"))
      (node (ref "Q5") (pin "6") (pinfunction "D_6") (pintype "passive"))
      (node (ref "Q5") (pin "7") (pinfunction "D_7") (pintype "passive"))
      (node (ref "Q5") (pin "8") (pinfunction "D_8") (pintype "passive"))
      (node (ref "Q6") (pin "5") (pinfunction "D_5") (pintype "passive"))
      (node (ref "Q6") (pin "6") (pinfunction "D_6") (pintype "passive"))
      (node (ref "Q6") (pin "7") (pinfunction "D_7") (pintype "passive"))
      (node (ref "Q6") (pin "8") (pinfunction "D_8") (pintype "passive"))
      (node (ref "U1") (pin "1") (pinfunction "VM_1") (pintype "power_in"))
      (node (ref "U2") (pin "1") (pinfunction "VM_1") (pintype "power_in"))
    )
    (net (code "38") (name "unconnected-(*-Pad1)") (class "Default")
      (node (ref "*") (pin "1") (pinfunction "1_1") (pintype "passive"))
    )
    (net (code "39") (name "unconnected-(*-Pad2)") (class "Default")
      (node (ref "*") (pin "2") (pinfunction "2_2") (pintype "passive"))
    )
    (net (code "40") (name "unconnected-(*-Pad3)") (class "Default")
      (node (ref "*") (pin "3") (pinfunction "3_3") (pintype "passive"))
    )
    (net (code "41") (name "unconnected-(J1-Pad3)") (class "Default")
      (node (ref "J1") (pin "3") (pinfunction "3_3") (pintype "passive+no_connect"))
    )
    (net (code "42") (name "unconnected-(S1-NO-Pad2)") (class "Default")
      (node (ref "S1") (pin "2") (pinfunction "NO_2") (pintype "passive"))
    )
    (net (code "43") (name "unconnected-(U1-FAULT-Pad9)") (class "Default")
      (node (ref "U1") (pin "9") (pinfunction "FAULT_9") (pintype "open_collector+no_connect"))
    )
    (net (code "44") (name "unconnected-(U1-SNSOUT-Pad10)") (class "Default")
      (node (ref "U1") (pin "10") (pinfunction "SNSOUT_10") (pintype "open_collector+no_connect"))
    )
    (net (code "45") (name "unconnected-(U1-SO-Pad11)") (class "Default")
      (node (ref "U1") (pin "11") (pinfunction "SO_11") (pintype "output+no_connect"))
    )
    (net (code "46") (name "unconnected-(U2-FAULT-Pad9)") (class "Default")
      (node (ref "U2") (pin "9") (pinfunction "FAULT_9") (pintype "open_collector+no_connect"))
    )
    (net (code "47") (name "unconnected-(U2-SNSOUT-Pad10)") (class "Default")
      (node (ref "U2") (pin "10") (pinfunction "SNSOUT_10") (pintype "open_collector+no_connect"))
    )
    (net (code "48") (name "unconnected-(U2-SO-Pad11)") (class "Default")
      (node (ref "U2") (pin "11") (pinfunction "SO_11") (pintype "output+no_connect"))
    )
  )
)
